# EMS_esp32_wifi_lora_gsm_v2_6.net
KiCad netlist of a schematic drawn in EAGLE
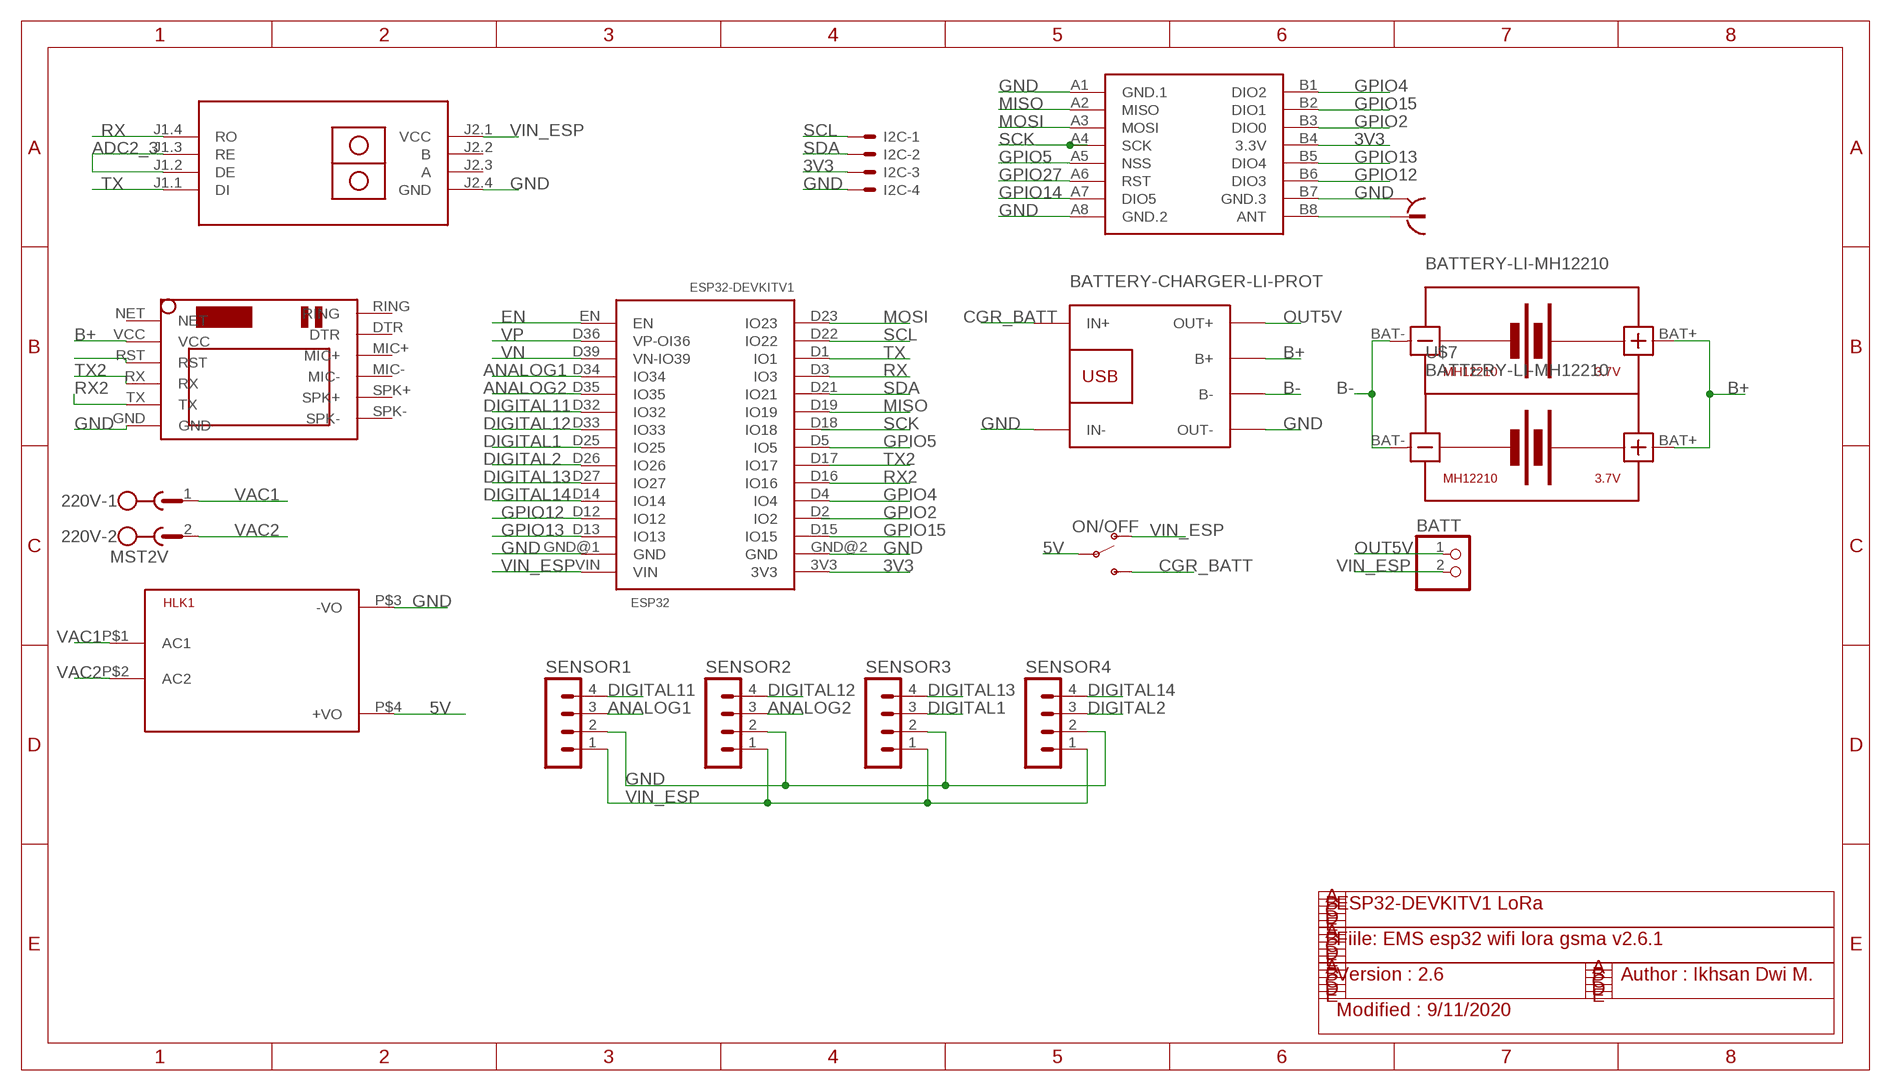
[diagram p0: schematic, sheet 1]

(export (version "E")
  (design (tool "Eeschema 10.0.6"))
  (components
    (comp (ref "220V")
      (value "MST2V")
      (footprint "eagle-import:MSTBV2")
      (libsource (lib "eagle-import") (part "MST2V"))
    )
    (comp (ref "BATT")
      (value "PINHD-1X2")
      (footprint "eagle-import:1X02")
      (libsource (lib "eagle-import") (part "PINHD-1X2"))
    )
    (comp (ref "ESP32")
      (value "ESP32DEVKITV1")
      (footprint "eagle-import:ESP32-DEVKITV1")
      (libsource (lib "eagle-import") (part "ESP32DEVKITV1"))
    )
    (comp (ref "HLK1")
      (value "HLK-PM013W")
      (footprint "eagle-import:HLK-PM01")
      (libsource (lib "eagle-import") (part "HLK-PM013W"))
    )
    (comp (ref "I2C")
      (value "22-23-2041")
      (footprint "eagle-import:22-23-2041")
      (fields (field (name "MF") "MOLEX"))
      (libsource (lib "eagle-import") (part "22-23-2041"))
    )
    (comp (ref "ON/OFF")
      (value "SWITCH-SPDT-PTH-11.6X4.0MM")
      (footprint "eagle-import:SWITCH_SPDT_PTH_11.6X4.0MM")
      (libsource (lib "eagle-import") (part "SWITCH-SPDT-PTH-11.6X4.0MM"))
    )
    (comp (ref "SENSOR1")
      (value "MA04-1")
      (footprint "eagle-import:MA04-1")
      (libsource (lib "eagle-import") (part "MA04-1"))
    )
    (comp (ref "SENSOR2")
      (value "MA04-1")
      (footprint "eagle-import:MA04-1")
      (libsource (lib "eagle-import") (part "MA04-1"))
    )
    (comp (ref "SENSOR3")
      (value "MA04-1")
      (footprint "eagle-import:MA04-1")
      (libsource (lib "eagle-import") (part "MA04-1"))
    )
    (comp (ref "SENSOR4")
      (value "MA04-1")
      (footprint "eagle-import:MA04-1")
      (libsource (lib "eagle-import") (part "MA04-1"))
    )
    (comp (ref "U$1")
      (value "RS485-TTL-CONVERTER")
      (footprint "eagle-import:RS485-TTL-CONVERTER")
      (libsource (lib "eagle-import") (part "RS485-TTL-CONVERTER"))
    )
    (comp (ref "U$5")
      (value "WIRELESS-LORA-RFM95W#SMD")
      (footprint "eagle-import:WIRELESS-LORA-RFM95W#SMD")
      (libsource (lib "eagle-import") (part "WIRELESS-LORA-RFM95W#SMD"))
    )
    (comp (ref "U$6")
      (value "BATTERY-LI-MH12210")
      (footprint "eagle-import:BATTERY-LI-MH12210")
      (libsource (lib "eagle-import") (part "BATTERY-LI-MH12210"))
    )
    (comp (ref "U$7")
      (value "BATTERY-LI-MH12210")
      (footprint "eagle-import:BATTERY-LI-MH12210")
      (libsource (lib "eagle-import") (part "BATTERY-LI-MH12210"))
    )
    (comp (ref "U$8")
      (value "BATTERY-CHARGER-LI-PROT")
      (footprint "eagle-import:BATTERY-CHARGER-LI-PROT")
      (libsource (lib "eagle-import") (part "BATTERY-CHARGER-LI-PROT"))
    )
    (comp (ref "U$9")
      (value "SIM800LMODULE")
      (footprint "eagle-import:SIM800LMODULE")
      (libsource (lib "eagle-import") (part "SIM800LMODULE"))
    )
    (comp (ref "X1")
      (value "734120110")
      (footprint "eagle-import:734120110")
      (libsource (lib "eagle-import") (part "734120110"))
    )
  )
  (nets
    (net (code "1") (name "/3V3") (class "Default")
      (node (ref "ESP32") (pin "3V3") (pinfunction "3V3_3V3") (pintype "bidirectional"))
      (node (ref "I2C") (pin "3") (pinfunction "S_3") (pintype "passive"))
      (node (ref "U$5") (pin "B4") (pinfunction "3.3V_B4") (pintype "power_in"))
    )
    (net (code "2") (name "/5V") (class "Default")
      (node (ref "HLK1") (pin "P$4") (pinfunction "+VO_P$4") (pintype "bidirectional"))
      (node (ref "ON/OFF") (pin "2") (pinfunction "P_2") (pintype "passive"))
    )
    (net (code "3") (name "/ADC2_3") (class "Default")
      (node (ref "U$1") (pin "J1.2") (pinfunction "DE_J1.2") (pintype "passive"))
      (node (ref "U$1") (pin "J1.3") (pinfunction "RE_J1.3") (pintype "passive"))
    )
    (net (code "4") (name "/ANALOG1") (class "Default")
      (node (ref "ESP32") (pin "D34") (pinfunction "IO34_D34") (pintype "bidirectional"))
      (node (ref "SENSOR1") (pin "3") (pinfunction "3_3") (pintype "passive"))
    )
    (net (code "5") (name "/ANALOG2") (class "Default")
      (node (ref "ESP32") (pin "D35") (pinfunction "IO35_D35") (pintype "bidirectional"))
      (node (ref "SENSOR2") (pin "3") (pinfunction "3_3") (pintype "passive"))
    )
    (net (code "6") (name "/B+") (class "Default")
      (node (ref "U$6") (pin "BAT+") (pinfunction "BAT+_BAT+") (pintype "power_in"))
      (node (ref "U$7") (pin "BAT+") (pinfunction "BAT+_BAT+") (pintype "power_in"))
      (node (ref "U$8") (pin "B+") (pinfunction "B+_B+") (pintype "bidirectional"))
      (node (ref "U$9") (pin "VCC") (pinfunction "VCC_VCC") (pintype "bidirectional"))
    )
    (net (code "7") (name "/B-") (class "Default")
      (node (ref "U$6") (pin "BAT-") (pinfunction "BAT-_BAT-") (pintype "power_in"))
      (node (ref "U$7") (pin "BAT-") (pinfunction "BAT-_BAT-") (pintype "power_in"))
      (node (ref "U$8") (pin "B-") (pinfunction "B-_B-") (pintype "bidirectional"))
    )
    (net (code "8") (name "/CGR_BATT") (class "Default")
      (node (ref "ON/OFF") (pin "3") (pinfunction "S_3") (pintype "passive"))
      (node (ref "U$8") (pin "IN+") (pinfunction "IN+_IN+") (pintype "bidirectional"))
    )
    (net (code "9") (name "/DIGITAL1") (class "Default")
      (node (ref "ESP32") (pin "D25") (pinfunction "IO25_D25") (pintype "bidirectional"))
      (node (ref "SENSOR3") (pin "3") (pinfunction "3_3") (pintype "passive"))
    )
    (net (code "10") (name "/DIGITAL2") (class "Default")
      (node (ref "ESP32") (pin "D26") (pinfunction "IO26_D26") (pintype "bidirectional"))
      (node (ref "SENSOR4") (pin "3") (pinfunction "3_3") (pintype "passive"))
    )
    (net (code "11") (name "/DIGITAL11") (class "Default")
      (node (ref "ESP32") (pin "D32") (pinfunction "IO32_D32") (pintype "bidirectional"))
      (node (ref "SENSOR1") (pin "4") (pinfunction "4_4") (pintype "passive"))
    )
    (net (code "12") (name "/DIGITAL12") (class "Default")
      (node (ref "ESP32") (pin "D33") (pinfunction "IO33_D33") (pintype "bidirectional"))
      (node (ref "SENSOR2") (pin "4") (pinfunction "4_4") (pintype "passive"))
    )
    (net (code "13") (name "/DIGITAL13") (class "Default")
      (node (ref "ESP32") (pin "D27") (pinfunction "IO27_D27") (pintype "bidirectional"))
      (node (ref "SENSOR3") (pin "4") (pinfunction "4_4") (pintype "passive"))
    )
    (net (code "14") (name "/DIGITAL14") (class "Default")
      (node (ref "ESP32") (pin "D14") (pinfunction "IO14_D14") (pintype "bidirectional"))
      (node (ref "SENSOR4") (pin "4") (pinfunction "4_4") (pintype "passive"))
    )
    (net (code "15") (name "/EN") (class "Default")
      (node (ref "ESP32") (pin "EN") (pinfunction "EN_EN") (pintype "bidirectional"))
    )
    (net (code "16") (name "/GND") (class "Default")
      (node (ref "ESP32") (pin "GND@1") (pinfunction "GND_GND@1") (pintype "bidirectional"))
      (node (ref "ESP32") (pin "GND@2") (pinfunction "GND_GND@2") (pintype "bidirectional"))
      (node (ref "HLK1") (pin "P$3") (pinfunction "-VO_P$3") (pintype "bidirectional"))
      (node (ref "I2C") (pin "4") (pinfunction "S_4") (pintype "passive"))
      (node (ref "SENSOR1") (pin "2") (pinfunction "2_2") (pintype "passive"))
      (node (ref "SENSOR2") (pin "2") (pinfunction "2_2") (pintype "passive"))
      (node (ref "SENSOR3") (pin "2") (pinfunction "2_2") (pintype "passive"))
      (node (ref "SENSOR4") (pin "2") (pinfunction "2_2") (pintype "passive"))
      (node (ref "U$1") (pin "J2.4") (pinfunction "GND_J2.4") (pintype "power_in"))
      (node (ref "U$5") (pin "A1") (pinfunction "GND.1_A1") (pintype "power_in"))
      (node (ref "U$5") (pin "A8") (pinfunction "GND.2_A8") (pintype "power_in"))
      (node (ref "U$5") (pin "B7") (pinfunction "GND.3_B7") (pintype "power_in"))
      (node (ref "U$8") (pin "IN-") (pinfunction "IN-_IN-") (pintype "bidirectional"))
      (node (ref "U$8") (pin "OUT-") (pinfunction "OUT-_OUT-") (pintype "bidirectional"))
      (node (ref "U$9") (pin "GND") (pinfunction "GND_GND") (pintype "bidirectional"))
      (node (ref "X1") (pin "S@1") (pinfunction "2_S@1") (pintype "passive"))
      (node (ref "X1") (pin "S@2") (pinfunction "2_S@2") (pintype "passive"))
      (node (ref "X1") (pin "S@3") (pinfunction "2_S@3") (pintype "passive"))
    )
    (net (code "17") (name "/GPIO2") (class "Default")
      (node (ref "ESP32") (pin "D2") (pinfunction "IO2_D2") (pintype "bidirectional"))
      (node (ref "U$5") (pin "B3") (pinfunction "DIO0_B3") (pintype "bidirectional"))
    )
    (net (code "18") (name "/GPIO4") (class "Default")
      (node (ref "ESP32") (pin "D4") (pinfunction "IO4_D4") (pintype "bidirectional"))
      (node (ref "U$5") (pin "B1") (pinfunction "DIO2_B1") (pintype "bidirectional"))
    )
    (net (code "19") (name "/GPIO5") (class "Default")
      (node (ref "ESP32") (pin "D5") (pinfunction "IO5_D5") (pintype "bidirectional"))
      (node (ref "U$5") (pin "A5") (pinfunction "NSS_A5") (pintype "bidirectional"))
    )
    (net (code "20") (name "/GPIO12") (class "Default")
      (node (ref "ESP32") (pin "D12") (pinfunction "IO12_D12") (pintype "bidirectional"))
      (node (ref "U$5") (pin "B6") (pinfunction "DIO3_B6") (pintype "bidirectional"))
    )
    (net (code "21") (name "/GPIO13") (class "Default")
      (node (ref "ESP32") (pin "D13") (pinfunction "IO13_D13") (pintype "bidirectional"))
      (node (ref "U$5") (pin "B5") (pinfunction "DIO4_B5") (pintype "bidirectional"))
    )
    (net (code "22") (name "/GPIO14") (class "Default")
      (node (ref "U$5") (pin "A7") (pinfunction "DIO5_A7") (pintype "bidirectional"))
    )
    (net (code "23") (name "/GPIO15") (class "Default")
      (node (ref "ESP32") (pin "D15") (pinfunction "IO15_D15") (pintype "bidirectional"))
      (node (ref "U$5") (pin "B2") (pinfunction "DIO1_B2") (pintype "bidirectional"))
    )
    (net (code "24") (name "/GPIO27") (class "Default")
      (node (ref "U$5") (pin "A6") (pinfunction "RST_A6") (pintype "bidirectional"))
    )
    (net (code "25") (name "/MISO") (class "Default")
      (node (ref "ESP32") (pin "D19") (pinfunction "IO19_D19") (pintype "bidirectional"))
      (node (ref "U$5") (pin "A2") (pinfunction "MISO_A2") (pintype "bidirectional"))
    )
    (net (code "26") (name "/MOSI") (class "Default")
      (node (ref "ESP32") (pin "D23") (pinfunction "IO23_D23") (pintype "bidirectional"))
      (node (ref "U$5") (pin "A3") (pinfunction "MOSI_A3") (pintype "bidirectional"))
    )
    (net (code "27") (name "/OUT5V") (class "Default")
      (node (ref "BATT") (pin "1") (pinfunction "1_1") (pintype "passive"))
      (node (ref "U$8") (pin "OUT+") (pinfunction "OUT+_OUT+") (pintype "bidirectional"))
    )
    (net (code "28") (name "/RX") (class "Default")
      (node (ref "ESP32") (pin "D3") (pinfunction "IO3_D3") (pintype "bidirectional"))
      (node (ref "U$1") (pin "J1.4") (pinfunction "RO_J1.4") (pintype "passive"))
    )
    (net (code "29") (name "/RX2") (class "Default")
      (node (ref "ESP32") (pin "D16") (pinfunction "IO16_D16") (pintype "bidirectional"))
      (node (ref "U$9") (pin "TX") (pinfunction "TX_TX") (pintype "bidirectional"))
    )
    (net (code "30") (name "/SCK") (class "Default")
      (node (ref "ESP32") (pin "D18") (pinfunction "IO18_D18") (pintype "bidirectional"))
      (node (ref "U$5") (pin "A4") (pinfunction "SCK_A4") (pintype "bidirectional"))
    )
    (net (code "31") (name "/SCL") (class "Default")
      (node (ref "ESP32") (pin "D22") (pinfunction "IO22_D22") (pintype "bidirectional"))
      (node (ref "I2C") (pin "1") (pinfunction "S_1") (pintype "passive"))
    )
    (net (code "32") (name "/SDA") (class "Default")
      (node (ref "ESP32") (pin "D21") (pinfunction "IO21_D21") (pintype "bidirectional"))
      (node (ref "I2C") (pin "2") (pinfunction "S_2") (pintype "passive"))
    )
    (net (code "33") (name "/TX") (class "Default")
      (node (ref "ESP32") (pin "D1") (pinfunction "IO1_D1") (pintype "bidirectional"))
      (node (ref "U$1") (pin "J1.1") (pinfunction "DI_J1.1") (pintype "passive"))
    )
    (net (code "34") (name "/TX2") (class "Default")
      (node (ref "ESP32") (pin "D17") (pinfunction "IO17_D17") (pintype "bidirectional"))
      (node (ref "U$9") (pin "RX") (pinfunction "RX_RX") (pintype "bidirectional"))
    )
    (net (code "35") (name "/VAC1") (class "Default")
      (node (ref "220V") (pin "1") (pinfunction "1_1") (pintype "passive"))
      (node (ref "HLK1") (pin "P$1") (pinfunction "AC1_P$1") (pintype "bidirectional"))
    )
    (net (code "36") (name "/VAC2") (class "Default")
      (node (ref "220V") (pin "2") (pinfunction "1_2") (pintype "passive"))
      (node (ref "HLK1") (pin "P$2") (pinfunction "AC2_P$2") (pintype "bidirectional"))
    )
    (net (code "37") (name "/VIN_ESP") (class "Default")
      (node (ref "BATT") (pin "2") (pinfunction "2_2") (pintype "passive"))
      (node (ref "ESP32") (pin "VIN") (pinfunction "VIN_VIN") (pintype "bidirectional"))
      (node (ref "ON/OFF") (pin "1") (pinfunction "O_1") (pintype "passive"))
      (node (ref "SENSOR1") (pin "1") (pinfunction "1_1") (pintype "passive"))
      (node (ref "SENSOR2") (pin "1") (pinfunction "1_1") (pintype "passive"))
      (node (ref "SENSOR3") (pin "1") (pinfunction "1_1") (pintype "passive"))
      (node (ref "SENSOR4") (pin "1") (pinfunction "1_1") (pintype "passive"))
      (node (ref "U$1") (pin "J2.1") (pinfunction "VCC_J2.1") (pintype "power_in"))
    )
    (net (code "38") (name "/VN") (class "Default")
      (node (ref "ESP32") (pin "D39") (pinfunction "VN-IO39_D39") (pintype "bidirectional"))
    )
    (net (code "39") (name "/VP") (class "Default")
      (node (ref "ESP32") (pin "D36") (pinfunction "VP-OI36_D36") (pintype "bidirectional"))
    )
    (net (code "40") (name "Net-(U$5-ANT)") (class "Default")
      (node (ref "U$5") (pin "B8") (pinfunction "ANT_B8") (pintype "passive"))
      (node (ref "X1") (pin "1") (pinfunction "1_1") (pintype "passive"))
    )
    (net (code "41") (name "unconnected-(U$1-A-PadJ2.3)") (class "Default")
      (node (ref "U$1") (pin "J2.3") (pinfunction "A_J2.3") (pintype "passive"))
    )
    (net (code "42") (name "unconnected-(U$1-B-PadJ2.2)") (class "Default")
      (node (ref "U$1") (pin "J2.2") (pinfunction "B_J2.2") (pintype "passive"))
    )
    (net (code "43") (name "unconnected-(U$9-PadDTR)") (class "Default")
      (node (ref "U$9") (pin "DTR") (pinfunction "DTR_DTR") (pintype "bidirectional"))
    )
    (net (code "44") (name "unconnected-(U$9-PadMIC+)") (class "Default")
      (node (ref "U$9") (pin "MIC+") (pinfunction "MIC+_MIC+") (pintype "bidirectional"))
    )
    (net (code "45") (name "unconnected-(U$9-PadMIC-)") (class "Default")
      (node (ref "U$9") (pin "MIC-") (pinfunction "MIC-_MIC-") (pintype "bidirectional"))
    )
    (net (code "46") (name "unconnected-(U$9-PadNET)") (class "Default")
      (node (ref "U$9") (pin "NET") (pinfunction "NET_NET") (pintype "bidirectional"))
    )
    (net (code "47") (name "unconnected-(U$9-PadRING)") (class "Default")
      (node (ref "U$9") (pin "RING") (pinfunction "RING_RING") (pintype "bidirectional"))
    )
    (net (code "48") (name "unconnected-(U$9-PadRST)") (class "Default")
      (node (ref "U$9") (pin "RST") (pinfunction "RST_RST") (pintype "bidirectional"))
    )
    (net (code "49") (name "unconnected-(U$9-PadSPK+)") (class "Default")
      (node (ref "U$9") (pin "SPK+") (pinfunction "SPK+_SPK+") (pintype "bidirectional"))
    )
    (net (code "50") (name "unconnected-(U$9-PadSPK-)") (class "Default")
      (node (ref "U$9") (pin "SPK-") (pinfunction "SPK-_SPK-") (pintype "bidirectional"))
    )
  )
)
